# cnc_rev_1.net
KiCad netlist of a schematic drawn in EAGLE
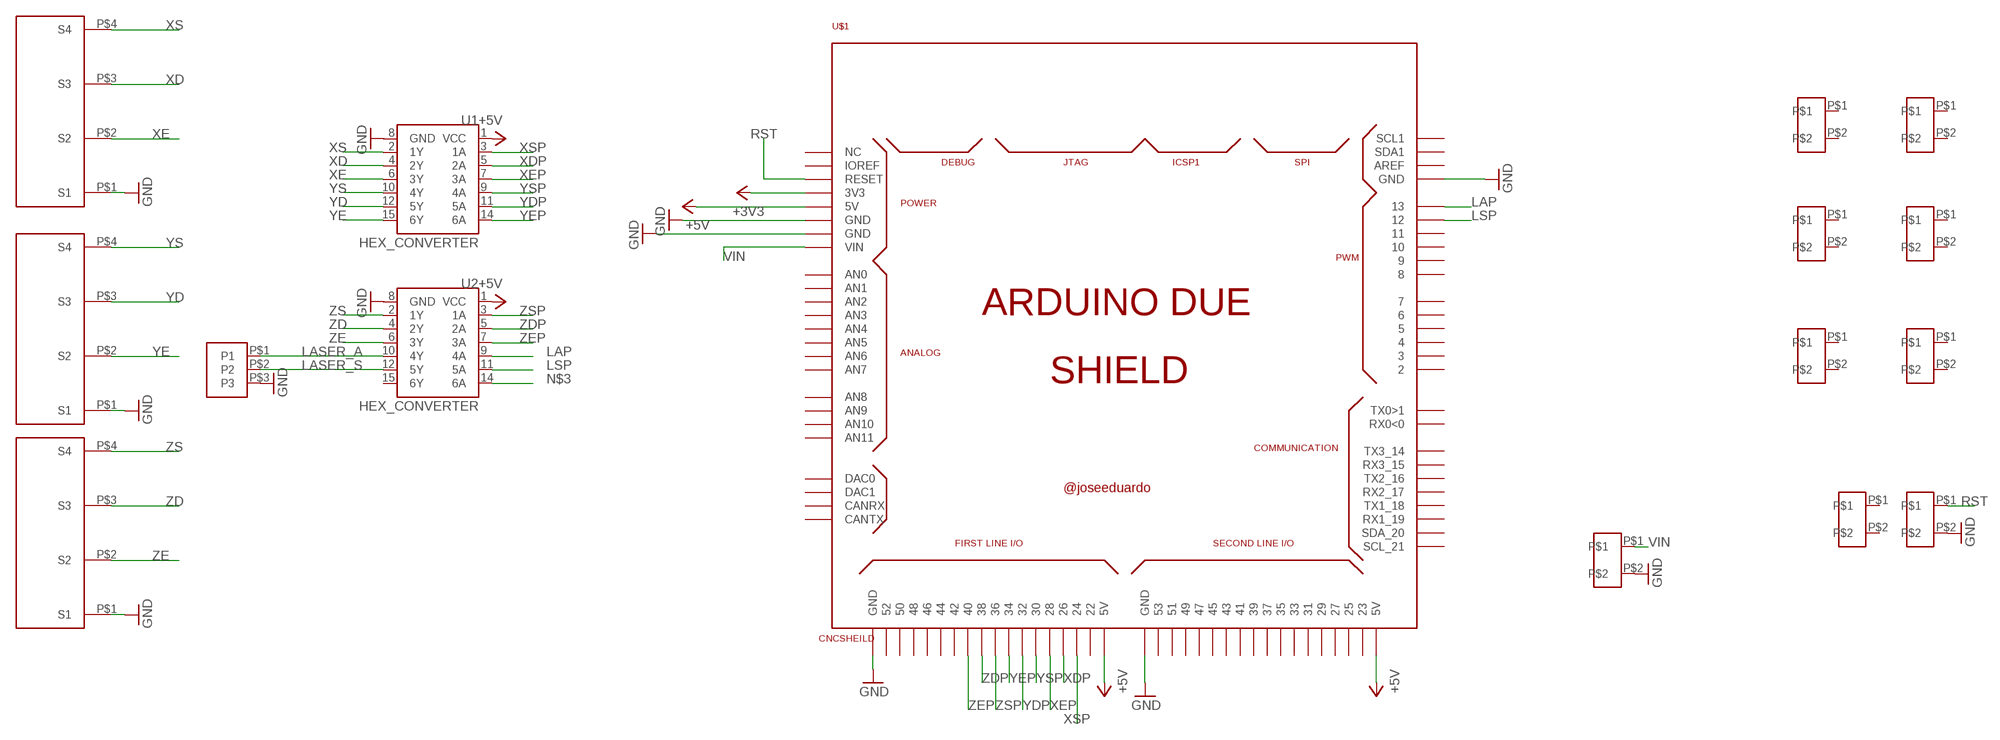
[diagram p0: schematic, sheet 1]

(export (version "E")
  (design (tool "Eeschema 10.0.6"))
  (components
    (comp (ref "INPUT")
      (value "PIN_LOCK_1X2")
      (footprint "eagle-import:PIN_LOCK1X2")
      (libsource (lib "eagle-import") (part "PIN_LOCK_1X2"))
    )
    (comp (ref "U$1")
      (value "CNCSHEILD")
      (footprint "eagle-import:CNCSHEILD")
      (libsource (lib "eagle-import") (part "CNCSHEILD"))
    )
    (comp (ref "U$2")
      (value "TBC1X4")
      (footprint "eagle-import:PTC1X4")
      (libsource (lib "eagle-import") (part "TBC1X4"))
    )
    (comp (ref "U$3")
      (value "TBC1X4")
      (footprint "eagle-import:PTC1X4")
      (libsource (lib "eagle-import") (part "TBC1X4"))
    )
    (comp (ref "U$4")
      (value "TBC1X4")
      (footprint "eagle-import:PTC1X4")
      (libsource (lib "eagle-import") (part "TBC1X4"))
    )
    (comp (ref "U$5")
      (value "PIN_LOCK_1X2")
      (footprint "eagle-import:PIN_LOCK1X2")
      (libsource (lib "eagle-import") (part "PIN_LOCK_1X2"))
    )
    (comp (ref "U$6")
      (value "PIN_LOCK_1X2")
      (footprint "eagle-import:PIN_LOCK1X2")
      (libsource (lib "eagle-import") (part "PIN_LOCK_1X2"))
    )
    (comp (ref "U$7")
      (value "PIN_LOCK_1X2")
      (footprint "eagle-import:PIN_LOCK1X2")
      (libsource (lib "eagle-import") (part "PIN_LOCK_1X2"))
    )
    (comp (ref "U$8")
      (value "PIN_LOCK_1X2")
      (footprint "eagle-import:PIN_LOCK1X2")
      (libsource (lib "eagle-import") (part "PIN_LOCK_1X2"))
    )
    (comp (ref "U$9")
      (value "PIN_LOCK_1X2")
      (footprint "eagle-import:PIN_LOCK1X2")
      (libsource (lib "eagle-import") (part "PIN_LOCK_1X2"))
    )
    (comp (ref "U$10")
      (value "PIN_LOCK_1X2")
      (footprint "eagle-import:PIN_LOCK1X2")
      (libsource (lib "eagle-import") (part "PIN_LOCK_1X2"))
    )
    (comp (ref "U$11")
      (value "PIN_LOCK_1X2")
      (footprint "eagle-import:PIN_LOCK1X2")
      (libsource (lib "eagle-import") (part "PIN_LOCK_1X2"))
    )
    (comp (ref "U$12")
      (value "PIN_LOCK_1X2")
      (footprint "eagle-import:PIN_LOCK1X2")
      (libsource (lib "eagle-import") (part "PIN_LOCK_1X2"))
    )
    (comp (ref "U$13")
      (value "PIN_LOCK_1X3")
      (footprint "eagle-import:PIN_LOCK1X3")
      (libsource (lib "eagle-import") (part "PIN_LOCK_1X3"))
    )
    (comp (ref "U1")
      (value "HEX_CONVERTER")
      (footprint "eagle-import:SO016")
      (libsource (lib "eagle-import") (part "HEX_CONVERTER"))
    )
    (comp (ref "U2")
      (value "HEX_CONVERTER")
      (footprint "eagle-import:SO016")
      (libsource (lib "eagle-import") (part "HEX_CONVERTER"))
    )
  )
  (nets
    (net (code "1") (name "+3V3") (class "Default")
      (node (ref "U$1") (pin "3V3") (pinfunction "3V3_3V3") (pintype "bidirectional"))
    )
    (net (code "2") (name "+5V") (class "Default")
      (node (ref "U$1") (pin "5V0") (pinfunction "5V_5V0") (pintype "bidirectional"))
      (node (ref "U$1") (pin "5V0_1") (pinfunction "5V_5V0_1") (pintype "bidirectional"))
      (node (ref "U$1") (pin "5V0_2") (pinfunction "5V_5V0_2") (pintype "bidirectional"))
      (node (ref "U1") (pin "1") (pinfunction "VCC_1") (pintype "bidirectional"))
      (node (ref "U2") (pin "1") (pinfunction "VCC_1") (pintype "bidirectional"))
    )
    (net (code "3") (name "/LAP") (class "Default")
      (node (ref "U$1") (pin "13") (pinfunction "13_13") (pintype "bidirectional"))
      (node (ref "U2") (pin "9") (pinfunction "4A_9") (pintype "bidirectional"))
    )
    (net (code "4") (name "/LASER_A") (class "Default")
      (node (ref "U$13") (pin "P$1") (pinfunction "P1_P$1") (pintype "bidirectional"))
      (node (ref "U2") (pin "10") (pinfunction "4Y_10") (pintype "bidirectional"))
    )
    (net (code "5") (name "/LASER_S") (class "Default")
      (node (ref "U$13") (pin "P$2") (pinfunction "P2_P$2") (pintype "bidirectional"))
      (node (ref "U2") (pin "12") (pinfunction "5Y_12") (pintype "bidirectional"))
    )
    (net (code "6") (name "/LSP") (class "Default")
      (node (ref "U$1") (pin "12") (pinfunction "12_12") (pintype "bidirectional"))
      (node (ref "U2") (pin "11") (pinfunction "5A_11") (pintype "bidirectional"))
    )
    (net (code "7") (name "/N$3") (class "Default")
      (node (ref "U2") (pin "14") (pinfunction "6A_14") (pintype "bidirectional"))
    )
    (net (code "8") (name "/RST") (class "Default")
      (node (ref "U$1") (pin "RESET") (pinfunction "RESET_RESET") (pintype "bidirectional"))
      (node (ref "U$11") (pin "P$1") (pinfunction "P$1_P$1") (pintype "bidirectional"))
    )
    (net (code "9") (name "/VIN") (class "Default")
      (node (ref "INPUT") (pin "P$1") (pinfunction "P$1_P$1") (pintype "bidirectional"))
      (node (ref "U$1") (pin "VIN") (pinfunction "VIN_VIN") (pintype "bidirectional"))
    )
    (net (code "10") (name "/XD") (class "Default")
      (node (ref "U$4") (pin "P$3") (pinfunction "S3_P$3") (pintype "bidirectional"))
      (node (ref "U1") (pin "4") (pinfunction "2Y_4") (pintype "bidirectional"))
    )
    (net (code "11") (name "/XDP") (class "Default")
      (node (ref "U$1") (pin "26") (pinfunction "26_26") (pintype "bidirectional"))
      (node (ref "U1") (pin "5") (pinfunction "2A_5") (pintype "bidirectional"))
    )
    (net (code "12") (name "/XE") (class "Default")
      (node (ref "U$4") (pin "P$2") (pinfunction "S2_P$2") (pintype "bidirectional"))
      (node (ref "U1") (pin "6") (pinfunction "3Y_6") (pintype "bidirectional"))
    )
    (net (code "13") (name "/XEP") (class "Default")
      (node (ref "U$1") (pin "28") (pinfunction "28_28") (pintype "bidirectional"))
      (node (ref "U1") (pin "7") (pinfunction "3A_7") (pintype "bidirectional"))
    )
    (net (code "14") (name "/XS") (class "Default")
      (node (ref "U$4") (pin "P$4") (pinfunction "S4_P$4") (pintype "bidirectional"))
      (node (ref "U1") (pin "2") (pinfunction "1Y_2") (pintype "bidirectional"))
    )
    (net (code "15") (name "/XSP") (class "Default")
      (node (ref "U$1") (pin "24") (pinfunction "24_24") (pintype "bidirectional"))
      (node (ref "U1") (pin "3") (pinfunction "1A_3") (pintype "bidirectional"))
    )
    (net (code "16") (name "/YD") (class "Default")
      (node (ref "U$2") (pin "P$3") (pinfunction "S3_P$3") (pintype "bidirectional"))
      (node (ref "U1") (pin "12") (pinfunction "5Y_12") (pintype "bidirectional"))
    )
    (net (code "17") (name "/YDP") (class "Default")
      (node (ref "U$1") (pin "32") (pinfunction "32_32") (pintype "bidirectional"))
      (node (ref "U1") (pin "11") (pinfunction "5A_11") (pintype "bidirectional"))
    )
    (net (code "18") (name "/YE") (class "Default")
      (node (ref "U$2") (pin "P$2") (pinfunction "S2_P$2") (pintype "bidirectional"))
      (node (ref "U1") (pin "15") (pinfunction "6Y_15") (pintype "bidirectional"))
    )
    (net (code "19") (name "/YEP") (class "Default")
      (node (ref "U$1") (pin "34") (pinfunction "34_34") (pintype "bidirectional"))
      (node (ref "U1") (pin "14") (pinfunction "6A_14") (pintype "bidirectional"))
    )
    (net (code "20") (name "/YS") (class "Default")
      (node (ref "U$2") (pin "P$4") (pinfunction "S4_P$4") (pintype "bidirectional"))
      (node (ref "U1") (pin "10") (pinfunction "4Y_10") (pintype "bidirectional"))
    )
    (net (code "21") (name "/YSP") (class "Default")
      (node (ref "U$1") (pin "30") (pinfunction "30_30") (pintype "bidirectional"))
      (node (ref "U1") (pin "9") (pinfunction "4A_9") (pintype "bidirectional"))
    )
    (net (code "22") (name "/ZD") (class "Default")
      (node (ref "U$3") (pin "P$3") (pinfunction "S3_P$3") (pintype "bidirectional"))
      (node (ref "U2") (pin "4") (pinfunction "2Y_4") (pintype "bidirectional"))
    )
    (net (code "23") (name "/ZDP") (class "Default")
      (node (ref "U$1") (pin "38") (pinfunction "38_38") (pintype "bidirectional"))
      (node (ref "U2") (pin "5") (pinfunction "2A_5") (pintype "bidirectional"))
    )
    (net (code "24") (name "/ZE") (class "Default")
      (node (ref "U$3") (pin "P$2") (pinfunction "S2_P$2") (pintype "bidirectional"))
      (node (ref "U2") (pin "6") (pinfunction "3Y_6") (pintype "bidirectional"))
    )
    (net (code "25") (name "/ZEP") (class "Default")
      (node (ref "U$1") (pin "40") (pinfunction "40_40") (pintype "bidirectional"))
      (node (ref "U2") (pin "7") (pinfunction "3A_7") (pintype "bidirectional"))
    )
    (net (code "26") (name "/ZS") (class "Default")
      (node (ref "U$3") (pin "P$4") (pinfunction "S4_P$4") (pintype "bidirectional"))
      (node (ref "U2") (pin "2") (pinfunction "1Y_2") (pintype "bidirectional"))
    )
    (net (code "27") (name "/ZSP") (class "Default")
      (node (ref "U$1") (pin "36") (pinfunction "36_36") (pintype "bidirectional"))
      (node (ref "U2") (pin "3") (pinfunction "1A_3") (pintype "bidirectional"))
    )
    (net (code "28") (name "GND") (class "Default")
      (node (ref "INPUT") (pin "P$2") (pinfunction "P$2_P$2") (pintype "bidirectional"))
      (node (ref "U$1") (pin "GND") (pinfunction "GND_GND") (pintype "bidirectional"))
      (node (ref "U$1") (pin "GND_1") (pinfunction "GND_GND_1") (pintype "bidirectional"))
      (node (ref "U$1") (pin "GND_2") (pinfunction "GND_GND_2") (pintype "bidirectional"))
      (node (ref "U$1") (pin "GND_3") (pinfunction "GND_GND_3") (pintype "bidirectional"))
      (node (ref "U$1") (pin "GND_4") (pinfunction "GND_GND_4") (pintype "bidirectional"))
      (node (ref "U$11") (pin "P$2") (pinfunction "P$2_P$2") (pintype "bidirectional"))
      (node (ref "U$2") (pin "P$1") (pinfunction "S1_P$1") (pintype "bidirectional"))
      (node (ref "U$3") (pin "P$1") (pinfunction "S1_P$1") (pintype "bidirectional"))
      (node (ref "U$4") (pin "P$1") (pinfunction "S1_P$1") (pintype "bidirectional"))
    )
    (net (code "29") (name "unconnected-(U$1-AN0-PadA0)") (class "Default")
      (node (ref "U$1") (pin "A0") (pinfunction "AN0_A0") (pintype "bidirectional"))
    )
    (net (code "30") (name "unconnected-(U$1-AN1-PadA1)") (class "Default")
      (node (ref "U$1") (pin "A1") (pinfunction "AN1_A1") (pintype "bidirectional"))
    )
    (net (code "31") (name "unconnected-(U$1-AN2-PadA2)") (class "Default")
      (node (ref "U$1") (pin "A2") (pinfunction "AN2_A2") (pintype "bidirectional"))
    )
    (net (code "32") (name "unconnected-(U$1-AN3-PadA3)") (class "Default")
      (node (ref "U$1") (pin "A3") (pinfunction "AN3_A3") (pintype "bidirectional"))
    )
    (net (code "33") (name "unconnected-(U$1-AN4-PadA4)") (class "Default")
      (node (ref "U$1") (pin "A4") (pinfunction "AN4_A4") (pintype "bidirectional"))
    )
    (net (code "34") (name "unconnected-(U$1-AN5-PadA5)") (class "Default")
      (node (ref "U$1") (pin "A5") (pinfunction "AN5_A5") (pintype "bidirectional"))
    )
    (net (code "35") (name "unconnected-(U$1-AN6-PadA6)") (class "Default")
      (node (ref "U$1") (pin "A6") (pinfunction "AN6_A6") (pintype "bidirectional"))
    )
    (net (code "36") (name "unconnected-(U$1-AN7-PadA7)") (class "Default")
      (node (ref "U$1") (pin "A7") (pinfunction "AN7_A7") (pintype "bidirectional"))
    )
    (net (code "37") (name "unconnected-(U$1-AN8-PadA8)") (class "Default")
      (node (ref "U$1") (pin "A8") (pinfunction "AN8_A8") (pintype "bidirectional"))
    )
    (net (code "38") (name "unconnected-(U$1-AN9-PadA9)") (class "Default")
      (node (ref "U$1") (pin "A9") (pinfunction "AN9_A9") (pintype "bidirectional"))
    )
    (net (code "39") (name "unconnected-(U$1-AN10-PadA10)") (class "Default")
      (node (ref "U$1") (pin "A10") (pinfunction "AN10_A10") (pintype "bidirectional"))
    )
    (net (code "40") (name "unconnected-(U$1-AN11-PadA11)") (class "Default")
      (node (ref "U$1") (pin "A11") (pinfunction "AN11_A11") (pintype "bidirectional"))
    )
    (net (code "41") (name "unconnected-(U$1-NC-PadNC_2)") (class "Default")
      (node (ref "U$1") (pin "NC_2") (pinfunction "NC_NC_2") (pintype "no_connect"))
    )
    (net (code "42") (name "unconnected-(U$1-Pad2)") (class "Default")
      (node (ref "U$1") (pin "2") (pinfunction "2_2") (pintype "bidirectional"))
    )
    (net (code "43") (name "unconnected-(U$1-Pad3)") (class "Default")
      (node (ref "U$1") (pin "3") (pinfunction "3_3") (pintype "bidirectional"))
    )
    (net (code "44") (name "unconnected-(U$1-Pad4)") (class "Default")
      (node (ref "U$1") (pin "4") (pinfunction "4_4") (pintype "bidirectional"))
    )
    (net (code "45") (name "unconnected-(U$1-Pad5)") (class "Default")
      (node (ref "U$1") (pin "5") (pinfunction "5_5") (pintype "bidirectional"))
    )
    (net (code "46") (name "unconnected-(U$1-Pad6)") (class "Default")
      (node (ref "U$1") (pin "6") (pinfunction "6_6") (pintype "bidirectional"))
    )
    (net (code "47") (name "unconnected-(U$1-Pad7)") (class "Default")
      (node (ref "U$1") (pin "7") (pinfunction "7_7") (pintype "bidirectional"))
    )
    (net (code "48") (name "unconnected-(U$1-Pad8)") (class "Default")
      (node (ref "U$1") (pin "8") (pinfunction "8_8") (pintype "bidirectional"))
    )
    (net (code "49") (name "unconnected-(U$1-Pad9)") (class "Default")
      (node (ref "U$1") (pin "9") (pinfunction "9_9") (pintype "bidirectional"))
    )
    (net (code "50") (name "unconnected-(U$1-Pad10)") (class "Default")
      (node (ref "U$1") (pin "10") (pinfunction "10_10") (pintype "bidirectional"))
    )
    (net (code "51") (name "unconnected-(U$1-Pad11)") (class "Default")
      (node (ref "U$1") (pin "11") (pinfunction "11_11") (pintype "bidirectional"))
    )
    (net (code "52") (name "unconnected-(U$1-Pad22)") (class "Default")
      (node (ref "U$1") (pin "22") (pinfunction "22_22") (pintype "bidirectional"))
    )
    (net (code "53") (name "unconnected-(U$1-Pad23)") (class "Default")
      (node (ref "U$1") (pin "23") (pinfunction "23_23") (pintype "bidirectional"))
    )
    (net (code "54") (name "unconnected-(U$1-Pad25)") (class "Default")
      (node (ref "U$1") (pin "25") (pinfunction "25_25") (pintype "bidirectional"))
    )
    (net (code "55") (name "unconnected-(U$1-Pad27)") (class "Default")
      (node (ref "U$1") (pin "27") (pinfunction "27_27") (pintype "bidirectional"))
    )
    (net (code "56") (name "unconnected-(U$1-Pad29)") (class "Default")
      (node (ref "U$1") (pin "29") (pinfunction "29_29") (pintype "bidirectional"))
    )
    (net (code "57") (name "unconnected-(U$1-Pad31)") (class "Default")
      (node (ref "U$1") (pin "31") (pinfunction "31_31") (pintype "bidirectional"))
    )
    (net (code "58") (name "unconnected-(U$1-Pad33)") (class "Default")
      (node (ref "U$1") (pin "33") (pinfunction "33_33") (pintype "bidirectional"))
    )
    (net (code "59") (name "unconnected-(U$1-Pad35)") (class "Default")
      (node (ref "U$1") (pin "35") (pinfunction "35_35") (pintype "bidirectional"))
    )
    (net (code "60") (name "unconnected-(U$1-Pad37)") (class "Default")
      (node (ref "U$1") (pin "37") (pinfunction "37_37") (pintype "bidirectional"))
    )
    (net (code "61") (name "unconnected-(U$1-Pad39)") (class "Default")
      (node (ref "U$1") (pin "39") (pinfunction "39_39") (pintype "bidirectional"))
    )
    (net (code "62") (name "unconnected-(U$1-Pad41)") (class "Default")
      (node (ref "U$1") (pin "41") (pinfunction "41_41") (pintype "bidirectional"))
    )
    (net (code "63") (name "unconnected-(U$1-Pad42)") (class "Default")
      (node (ref "U$1") (pin "42") (pinfunction "42_42") (pintype "bidirectional"))
    )
    (net (code "64") (name "unconnected-(U$1-Pad43)") (class "Default")
      (node (ref "U$1") (pin "43") (pinfunction "43_43") (pintype "bidirectional"))
    )
    (net (code "65") (name "unconnected-(U$1-Pad44)") (class "Default")
      (node (ref "U$1") (pin "44") (pinfunction "44_44") (pintype "bidirectional"))
    )
    (net (code "66") (name "unconnected-(U$1-Pad45)") (class "Default")
      (node (ref "U$1") (pin "45") (pinfunction "45_45") (pintype "bidirectional"))
    )
    (net (code "67") (name "unconnected-(U$1-Pad46)") (class "Default")
      (node (ref "U$1") (pin "46") (pinfunction "46_46") (pintype "bidirectional"))
    )
    (net (code "68") (name "unconnected-(U$1-Pad47)") (class "Default")
      (node (ref "U$1") (pin "47") (pinfunction "47_47") (pintype "bidirectional"))
    )
    (net (code "69") (name "unconnected-(U$1-Pad48)") (class "Default")
      (node (ref "U$1") (pin "48") (pinfunction "48_48") (pintype "bidirectional"))
    )
    (net (code "70") (name "unconnected-(U$1-Pad49)") (class "Default")
      (node (ref "U$1") (pin "49") (pinfunction "49_49") (pintype "bidirectional"))
    )
    (net (code "71") (name "unconnected-(U$1-Pad50)") (class "Default")
      (node (ref "U$1") (pin "50") (pinfunction "50_50") (pintype "bidirectional"))
    )
    (net (code "72") (name "unconnected-(U$1-Pad51)") (class "Default")
      (node (ref "U$1") (pin "51") (pinfunction "51_51") (pintype "bidirectional"))
    )
    (net (code "73") (name "unconnected-(U$1-Pad52)") (class "Default")
      (node (ref "U$1") (pin "52") (pinfunction "52_52") (pintype "bidirectional"))
    )
    (net (code "74") (name "unconnected-(U$1-Pad53)") (class "Default")
      (node (ref "U$1") (pin "53") (pinfunction "53_53") (pintype "bidirectional"))
    )
    (net (code "75") (name "unconnected-(U$1-PadAREF)") (class "Default")
      (node (ref "U$1") (pin "AREF") (pinfunction "AREF_AREF") (pintype "bidirectional"))
    )
    (net (code "76") (name "unconnected-(U$1-PadCANRX)") (class "Default")
      (node (ref "U$1") (pin "CANRX") (pinfunction "CANRX_CANRX") (pintype "bidirectional"))
    )
    (net (code "77") (name "unconnected-(U$1-PadCANTX)") (class "Default")
      (node (ref "U$1") (pin "CANTX") (pinfunction "CANTX_CANTX") (pintype "bidirectional"))
    )
    (net (code "78") (name "unconnected-(U$1-PadDAC0)") (class "Default")
      (node (ref "U$1") (pin "DAC0") (pinfunction "DAC0_DAC0") (pintype "bidirectional"))
    )
    (net (code "79") (name "unconnected-(U$1-PadDAC1)") (class "Default")
      (node (ref "U$1") (pin "DAC1") (pinfunction "DAC1_DAC1") (pintype "bidirectional"))
    )
    (net (code "80") (name "unconnected-(U$1-PadIOREF)") (class "Default")
      (node (ref "U$1") (pin "IOREF") (pinfunction "IOREF_IOREF") (pintype "bidirectional"))
    )
    (net (code "81") (name "unconnected-(U$1-PadSCL1)") (class "Default")
      (node (ref "U$1") (pin "SCL1") (pinfunction "SCL1_SCL1") (pintype "bidirectional"))
    )
    (net (code "82") (name "unconnected-(U$1-PadSDA1)") (class "Default")
      (node (ref "U$1") (pin "SDA1") (pinfunction "SDA1_SDA1") (pintype "bidirectional"))
    )
    (net (code "83") (name "unconnected-(U$1-RX0<0-Pad0)") (class "Default")
      (node (ref "U$1") (pin "0") (pinfunction "RX0<0_0") (pintype "bidirectional"))
    )
    (net (code "84") (name "unconnected-(U$1-RX1_19-Pad19)") (class "Default")
      (node (ref "U$1") (pin "19") (pinfunction "RX1_19_19") (pintype "bidirectional"))
    )
    (net (code "85") (name "unconnected-(U$1-RX2_17-Pad17)") (class "Default")
      (node (ref "U$1") (pin "17") (pinfunction "RX2_17_17") (pintype "bidirectional"))
    )
    (net (code "86") (name "unconnected-(U$1-RX3_15-Pad15)") (class "Default")
      (node (ref "U$1") (pin "15") (pinfunction "RX3_15_15") (pintype "bidirectional"))
    )
    (net (code "87") (name "unconnected-(U$1-SCL_21-Pad21)") (class "Default")
      (node (ref "U$1") (pin "21") (pinfunction "SCL_21_21") (pintype "bidirectional"))
    )
    (net (code "88") (name "unconnected-(U$1-SDA_20-Pad20)") (class "Default")
      (node (ref "U$1") (pin "20") (pinfunction "SDA_20_20") (pintype "bidirectional"))
    )
    (net (code "89") (name "unconnected-(U$1-TX0>1-Pad1)") (class "Default")
      (node (ref "U$1") (pin "1") (pinfunction "TX0>1_1") (pintype "bidirectional"))
    )
    (net (code "90") (name "unconnected-(U$1-TX1_18-Pad18)") (class "Default")
      (node (ref "U$1") (pin "18") (pinfunction "TX1_18_18") (pintype "bidirectional"))
    )
    (net (code "91") (name "unconnected-(U$1-TX2_16-Pad16)") (class "Default")
      (node (ref "U$1") (pin "16") (pinfunction "TX2_16_16") (pintype "bidirectional"))
    )
    (net (code "92") (name "unconnected-(U$1-TX3_14-Pad14)") (class "Default")
      (node (ref "U$1") (pin "14") (pinfunction "TX3_14_14") (pintype "bidirectional"))
    )
    (net (code "93") (name "unconnected-(U$5-PadP$1)") (class "Default")
      (node (ref "U$5") (pin "P$1") (pinfunction "P$1_P$1") (pintype "bidirectional"))
    )
    (net (code "94") (name "unconnected-(U$5-PadP$2)") (class "Default")
      (node (ref "U$5") (pin "P$2") (pinfunction "P$2_P$2") (pintype "bidirectional"))
    )
    (net (code "95") (name "unconnected-(U$6-PadP$1)") (class "Default")
      (node (ref "U$6") (pin "P$1") (pinfunction "P$1_P$1") (pintype "bidirectional"))
    )
    (net (code "96") (name "unconnected-(U$6-PadP$2)") (class "Default")
      (node (ref "U$6") (pin "P$2") (pinfunction "P$2_P$2") (pintype "bidirectional"))
    )
    (net (code "97") (name "unconnected-(U$7-PadP$1)") (class "Default")
      (node (ref "U$7") (pin "P$1") (pinfunction "P$1_P$1") (pintype "bidirectional"))
    )
    (net (code "98") (name "unconnected-(U$7-PadP$2)") (class "Default")
      (node (ref "U$7") (pin "P$2") (pinfunction "P$2_P$2") (pintype "bidirectional"))
    )
    (net (code "99") (name "unconnected-(U$8-PadP$1)") (class "Default")
      (node (ref "U$8") (pin "P$1") (pinfunction "P$1_P$1") (pintype "bidirectional"))
    )
    (net (code "100") (name "unconnected-(U$8-PadP$2)") (class "Default")
      (node (ref "U$8") (pin "P$2") (pinfunction "P$2_P$2") (pintype "bidirectional"))
    )
    (net (code "101") (name "unconnected-(U$9-PadP$1)") (class "Default")
      (node (ref "U$9") (pin "P$1") (pinfunction "P$1_P$1") (pintype "bidirectional"))
    )
    (net (code "102") (name "unconnected-(U$9-PadP$2)") (class "Default")
      (node (ref "U$9") (pin "P$2") (pinfunction "P$2_P$2") (pintype "bidirectional"))
    )
    (net (code "103") (name "unconnected-(U$10-PadP$1)") (class "Default")
      (node (ref "U$10") (pin "P$1") (pinfunction "P$1_P$1") (pintype "bidirectional"))
    )
    (net (code "104") (name "unconnected-(U$10-PadP$2)") (class "Default")
      (node (ref "U$10") (pin "P$2") (pinfunction "P$2_P$2") (pintype "bidirectional"))
    )
    (net (code "105") (name "unconnected-(U$12-PadP$1)") (class "Default")
      (node (ref "U$12") (pin "P$1") (pinfunction "P$1_P$1") (pintype "bidirectional"))
    )
    (net (code "106") (name "unconnected-(U$12-PadP$2)") (class "Default")
      (node (ref "U$12") (pin "P$2") (pinfunction "P$2_P$2") (pintype "bidirectional"))
    )
    (net (code "107") (name "unconnected-(U$13-P3-PadP$3)") (class "Default")
      (node (ref "U$13") (pin "P$3") (pinfunction "P3_P$3") (pintype "bidirectional"))
    )
    (net (code "108") (name "unconnected-(U1-GND-Pad8)") (class "Default")
      (node (ref "U1") (pin "8") (pinfunction "GND_8") (pintype "bidirectional"))
    )
    (net (code "109") (name "unconnected-(U2-6Y-Pad15)") (class "Default")
      (node (ref "U2") (pin "15") (pinfunction "6Y_15") (pintype "bidirectional"))
    )
    (net (code "110") (name "unconnected-(U2-GND-Pad8)") (class "Default")
      (node (ref "U2") (pin "8") (pinfunction "GND_8") (pintype "bidirectional"))
    )
  )
)
